# SchematicPowerSupply.net
KiCad netlist of a schematic drawn in Altium Designer
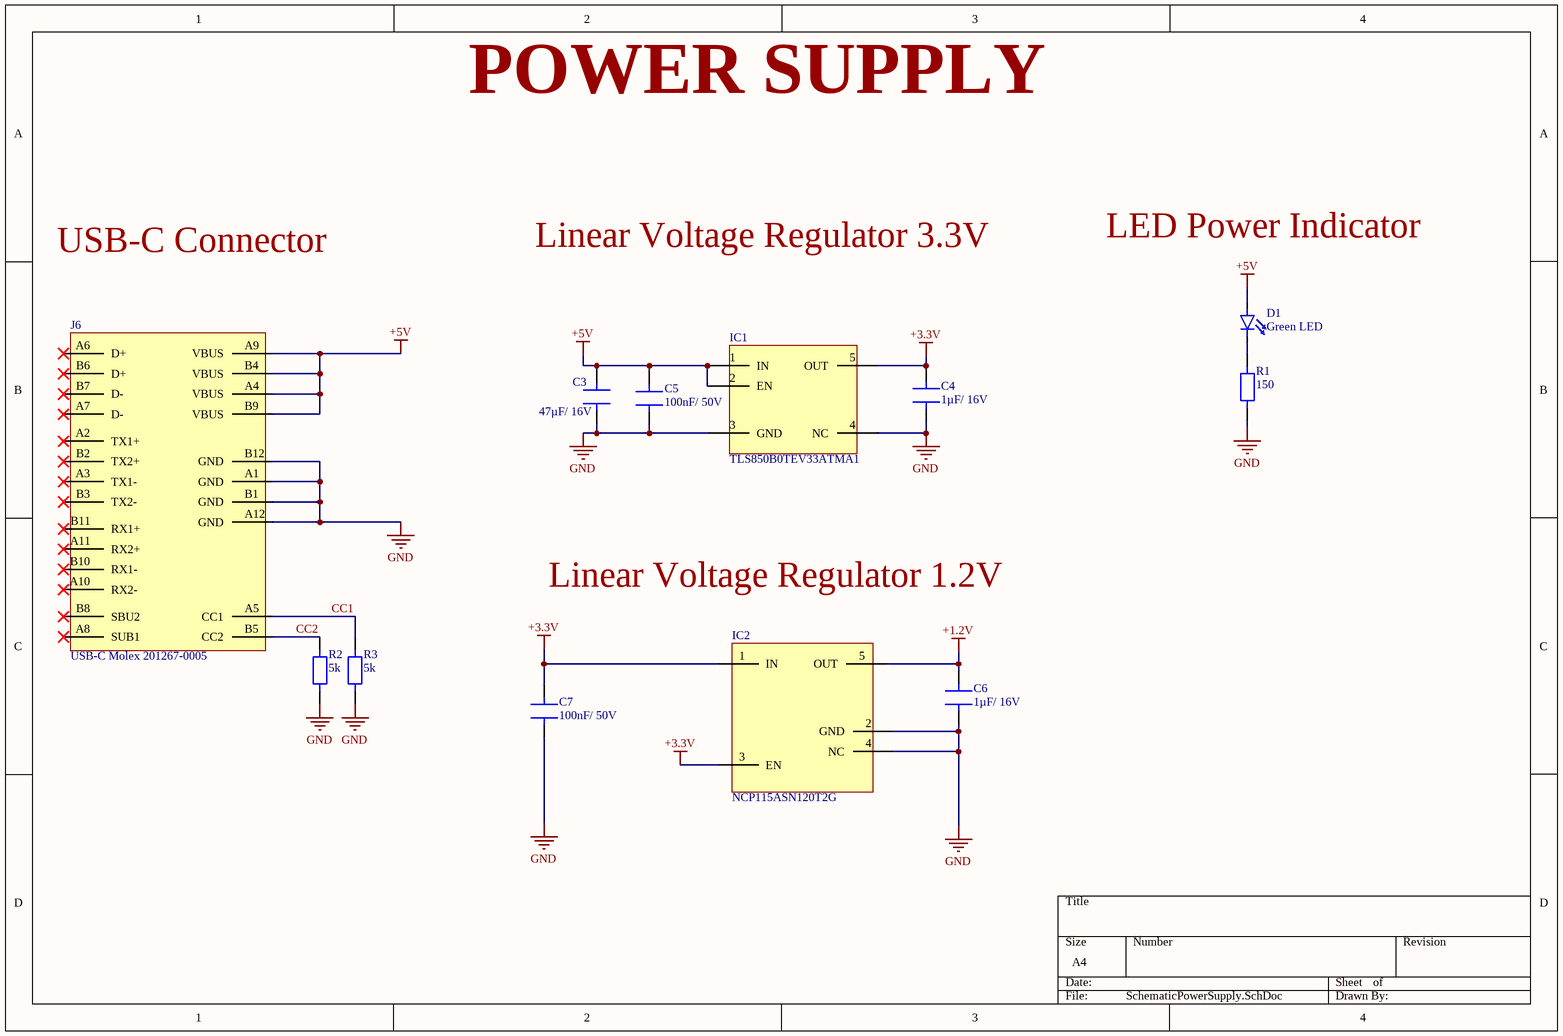
[diagram p0: SchematicPowerSupply.SchDoc]

(export (version "E")
  (design (tool "Eeschema 10.0.6"))
  (components
    (comp (ref "C3")
      (value "47µF/ 16V")
      (footprint "C1210")
      (description "C1210")
      (libsource (lib "upbracing_library") (part "C 47µF/ 16V"))
    )
    (comp (ref "C4")
      (value "1µF/ 16V")
      (footprint "C0603")
      (description "C0603/C0805")
      (libsource (lib "upbracing_library") (part "C 1µF/ 16V"))
    )
    (comp (ref "C5")
      (value "100nF/ 50V")
      (footprint "C0603")
      (description "C0603/C0805")
      (libsource (lib "upbracing_library") (part "C 100nF/ 50V"))
    )
    (comp (ref "C6")
      (value "1µF/ 16V")
      (footprint "C0603")
      (description "C0603/C0805")
      (libsource (lib "upbracing_library") (part "C 1µF/ 16V"))
    )
    (comp (ref "C7")
      (value "100nF/ 50V")
      (footprint "C0603")
      (description "C0603/C0805")
      (libsource (lib "upbracing_library") (part "C 100nF/ 50V"))
    )
    (comp (ref "D1")
      (value "Green LED")
      (footprint "LED_0805")
      (description "Status LED")
      (libsource (lib "upbracing_library") (part "LED 0805"))
    )
    (comp (ref "IC1")
      (value "TLS850B0TEV33ATMA1")
      (footprint "TO-252-5")
      (description "Input 3-40V, Output 3.3V")
      (libsource (lib "upbracing_library") (part "TLS850B0TEV33ATMA1"))
    )
    (comp (ref "IC2")
      (value "NCP115ASN120T2G")
      (footprint "TSOP-5")
      (description "Input 1.7V-5.5V, Ouput 1.2V")
      (libsource (lib "upbracing_library") (part "NCP115ASN120T2G"))
    )
    (comp (ref "J6")
      (value "USB-C Molex 201267-0005")
      (footprint "USB-C Molex 2012670005")
      (libsource (lib "upbracing_library") (part "USB-C Molex 201267-0005"))
    )
    (comp (ref "R1")
      (value "150")
      (footprint "R0603")
      (description "0603/0805")
      (libsource (lib "upbracing_library") (part "RES_150"))
    )
    (comp (ref "R2")
      (value "5k")
      (footprint "R0603")
      (description "0603/0805")
      (libsource (lib "upbracing_library") (part "RES_5k"))
    )
    (comp (ref "R3")
      (value "5k")
      (footprint "R0603")
      (description "0603/0805")
      (libsource (lib "upbracing_library") (part "RES_5k"))
    )
  )
  (nets
    (net (code "1") (name "+1.2V") (class "Default")
      (node (ref "C6") (pin "2") (pinfunction "2_2") (pintype "passive"))
      (node (ref "IC2") (pin "5") (pinfunction "OUT_5") (pintype "passive"))
    )
    (net (code "2") (name "+3.3V") (class "Default")
      (node (ref "C4") (pin "2") (pinfunction "2_2") (pintype "passive"))
      (node (ref "C7") (pin "2") (pinfunction "2_2") (pintype "passive"))
      (node (ref "IC1") (pin "5") (pinfunction "OUT_5") (pintype "passive"))
      (node (ref "IC2") (pin "1") (pinfunction "IN_1") (pintype "passive"))
      (node (ref "IC2") (pin "3") (pinfunction "EN_3") (pintype "passive"))
    )
    (net (code "3") (name "+5V") (class "Default")
      (node (ref "C3") (pin "2") (pinfunction "2_2") (pintype "passive"))
      (node (ref "C5") (pin "2") (pinfunction "2_2") (pintype "passive"))
      (node (ref "D1") (pin "1") (pinfunction "1_1") (pintype "passive"))
      (node (ref "IC1") (pin "1") (pinfunction "IN_1") (pintype "passive"))
      (node (ref "IC1") (pin "2") (pinfunction "EN_2") (pintype "passive"))
      (node (ref "J6") (pin "A4") (pinfunction "VBUS_A4") (pintype "passive"))
      (node (ref "J6") (pin "A9") (pinfunction "VBUS_A9") (pintype "passive"))
      (node (ref "J6") (pin "B4") (pinfunction "VBUS_B4") (pintype "passive"))
      (node (ref "J6") (pin "B9") (pinfunction "VBUS_B9") (pintype "passive"))
    )
    (net (code "4") (name "/CC1") (class "Default")
      (node (ref "J6") (pin "A5") (pinfunction "CC1_A5") (pintype "passive"))
      (node (ref "R3") (pin "2") (pinfunction "2_2") (pintype "passive"))
    )
    (net (code "5") (name "/CC2") (class "Default")
      (node (ref "J6") (pin "B5") (pinfunction "CC2_B5") (pintype "passive"))
      (node (ref "R2") (pin "2") (pinfunction "2_2") (pintype "passive"))
    )
    (net (code "6") (name "GND") (class "Default")
      (node (ref "C3") (pin "1") (pinfunction "1_1") (pintype "passive"))
      (node (ref "C4") (pin "1") (pinfunction "1_1") (pintype "passive"))
      (node (ref "C5") (pin "1") (pinfunction "1_1") (pintype "passive"))
      (node (ref "C6") (pin "1") (pinfunction "1_1") (pintype "passive"))
      (node (ref "C7") (pin "1") (pinfunction "1_1") (pintype "passive"))
      (node (ref "IC1") (pin "3") (pinfunction "GND_3") (pintype "passive"))
      (node (ref "IC1") (pin "4") (pinfunction "NC_4") (pintype "passive"))
      (node (ref "IC2") (pin "2") (pinfunction "GND_2") (pintype "passive"))
      (node (ref "IC2") (pin "4") (pinfunction "NC_4") (pintype "passive"))
      (node (ref "J6") (pin "A1") (pinfunction "GND_A1") (pintype "passive"))
      (node (ref "J6") (pin "A12") (pinfunction "GND_A12") (pintype "passive"))
      (node (ref "J6") (pin "B1") (pinfunction "GND_B1") (pintype "passive"))
      (node (ref "J6") (pin "B12") (pinfunction "GND_B12") (pintype "passive"))
      (node (ref "R1") (pin "1") (pinfunction "1_1") (pintype "passive"))
      (node (ref "R2") (pin "1") (pinfunction "1_1") (pintype "passive"))
      (node (ref "R3") (pin "1") (pinfunction "1_1") (pintype "passive"))
    )
    (net (code "7") (name "Net-(D1-Pad2)") (class "Default")
      (node (ref "D1") (pin "2") (pinfunction "2_2") (pintype "passive"))
      (node (ref "R1") (pin "2") (pinfunction "2_2") (pintype "passive"))
    )
    (net (code "8") (name "unconnected-(J6-D+-PadA6)") (class "Default")
      (node (ref "J6") (pin "A6") (pinfunction "D+_A6") (pintype "passive+no_connect"))
    )
    (net (code "9") (name "unconnected-(J6-D+-PadB6)") (class "Default")
      (node (ref "J6") (pin "B6") (pinfunction "D+_B6") (pintype "passive+no_connect"))
    )
    (net (code "10") (name "unconnected-(J6-D--PadA7)") (class "Default")
      (node (ref "J6") (pin "A7") (pinfunction "D-_A7") (pintype "passive+no_connect"))
    )
    (net (code "11") (name "unconnected-(J6-D--PadB7)") (class "Default")
      (node (ref "J6") (pin "B7") (pinfunction "D-_B7") (pintype "passive+no_connect"))
    )
    (net (code "12") (name "unconnected-(J6-RX1+-PadB11)") (class "Default")
      (node (ref "J6") (pin "B11") (pinfunction "RX1+_B11") (pintype "passive+no_connect"))
    )
    (net (code "13") (name "unconnected-(J6-RX1--PadB10)") (class "Default")
      (node (ref "J6") (pin "B10") (pinfunction "RX1-_B10") (pintype "passive+no_connect"))
    )
    (net (code "14") (name "unconnected-(J6-RX2+-PadA11)") (class "Default")
      (node (ref "J6") (pin "A11") (pinfunction "RX2+_A11") (pintype "passive+no_connect"))
    )
    (net (code "15") (name "unconnected-(J6-RX2--PadA10)") (class "Default")
      (node (ref "J6") (pin "A10") (pinfunction "RX2-_A10") (pintype "passive+no_connect"))
    )
    (net (code "16") (name "unconnected-(J6-SBU2-PadB8)") (class "Default")
      (node (ref "J6") (pin "B8") (pinfunction "SBU2_B8") (pintype "passive+no_connect"))
    )
    (net (code "17") (name "unconnected-(J6-SUB1-PadA8)") (class "Default")
      (node (ref "J6") (pin "A8") (pinfunction "SUB1_A8") (pintype "passive+no_connect"))
    )
    (net (code "18") (name "unconnected-(J6-TX1+-PadA2)") (class "Default")
      (node (ref "J6") (pin "A2") (pinfunction "TX1+_A2") (pintype "passive+no_connect"))
    )
    (net (code "19") (name "unconnected-(J6-TX1--PadA3)") (class "Default")
      (node (ref "J6") (pin "A3") (pinfunction "TX1-_A3") (pintype "passive+no_connect"))
    )
    (net (code "20") (name "unconnected-(J6-TX2+-PadB2)") (class "Default")
      (node (ref "J6") (pin "B2") (pinfunction "TX2+_B2") (pintype "passive+no_connect"))
    )
    (net (code "21") (name "unconnected-(J6-TX2--PadB3)") (class "Default")
      (node (ref "J6") (pin "B3") (pinfunction "TX2-_B3") (pintype "passive+no_connect"))
    )
  )
)
